# jar-of-fireflies.net
KiCad netlist of a schematic drawn in EAGLE
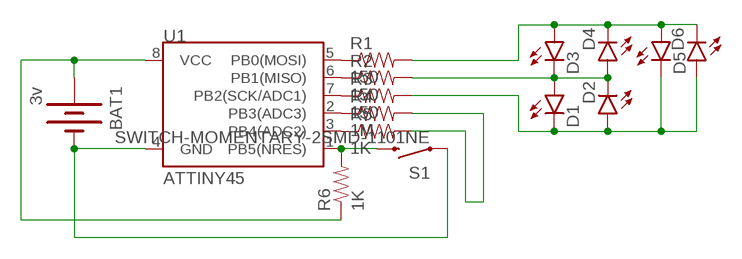
[diagram p0: schematic, sheet 1]

(export (version "E")
  (design (tool "Eeschema 10.0.6"))
  (components
    (comp (ref "BAT1")
      (value "3v")
      (footprint "eagle-import:BATTCOM_20MM_PTH")
      (libsource (lib "eagle-import") (part "BATTERY20PTH"))
    )
    (comp (ref "D1")
      (value "LED3MM")
      (footprint "eagle-import:LED3MM")
      (libsource (lib "eagle-import") (part "LED3MM"))
    )
    (comp (ref "D2")
      (value "LED3MM")
      (footprint "eagle-import:LED3MM")
      (libsource (lib "eagle-import") (part "LED3MM"))
    )
    (comp (ref "D3")
      (value "LED3MM")
      (footprint "eagle-import:LED3MM")
      (libsource (lib "eagle-import") (part "LED3MM"))
    )
    (comp (ref "D4")
      (value "LED3MM")
      (footprint "eagle-import:LED3MM")
      (libsource (lib "eagle-import") (part "LED3MM"))
    )
    (comp (ref "D5")
      (value "LED3MM")
      (footprint "eagle-import:LED3MM")
      (libsource (lib "eagle-import") (part "LED3MM"))
    )
    (comp (ref "D6")
      (value "LED3MM")
      (footprint "eagle-import:LED3MM")
      (libsource (lib "eagle-import") (part "LED3MM"))
    )
    (comp (ref "R1")
      (value "150")
      (footprint "eagle-import:AXIAL-0.4")
      (libsource (lib "eagle-import") (part "RESISTORPTH-1/4W"))
    )
    (comp (ref "R2")
      (value "150")
      (footprint "eagle-import:AXIAL-0.4")
      (libsource (lib "eagle-import") (part "RESISTORPTH-1/4W"))
    )
    (comp (ref "R3")
      (value "150")
      (footprint "eagle-import:AXIAL-0.4")
      (libsource (lib "eagle-import") (part "RESISTORPTH-1/4W"))
    )
    (comp (ref "R4")
      (value "1M")
      (footprint "eagle-import:AXIAL-0.4")
      (libsource (lib "eagle-import") (part "RESISTORPTH-1/4W"))
    )
    (comp (ref "R5")
      (value "1K")
      (footprint "eagle-import:AXIAL-0.4")
      (libsource (lib "eagle-import") (part "RESISTORPTH-1/4W"))
    )
    (comp (ref "R6")
      (value "1K")
      (footprint "eagle-import:AXIAL-0.4")
      (libsource (lib "eagle-import") (part "RESISTORPTH-1/4W"))
    )
    (comp (ref "S1")
      (value "SWITCH-MOMENTARY-2SMD-1101NE")
      (footprint "eagle-import:TACTILE-SWITCH-1101NE")
      (libsource (lib "eagle-import") (part "SWITCH-MOMENTARY-2SMD-1101NE"))
    )
    (comp (ref "U1")
      (value "ATTINY45")
      (footprint "eagle-import:DIP08")
      (libsource (lib "eagle-import") (part "ATTINY45TINY85-20-DIP"))
    )
  )
  (nets
    (net (code "1") (name "Net-(BAT1-+)") (class "Default")
      (node (ref "BAT1") (pin "1") (pinfunction "+_1") (pintype "power_in"))
      (node (ref "R6") (pin "P$1") (pinfunction "1_P$1") (pintype "passive"))
      (node (ref "U1") (pin "8") (pinfunction "VCC_8") (pintype "bidirectional"))
    )
    (net (code "2") (name "Net-(BAT1--)") (class "Default")
      (node (ref "BAT1") (pin "2") (pinfunction "-_2") (pintype "power_in"))
      (node (ref "S1") (pin "1") (pinfunction "1_1") (pintype "passive"))
      (node (ref "U1") (pin "4") (pinfunction "GND_4") (pintype "bidirectional"))
    )
    (net (code "3") (name "Net-(D1-C)") (class "Default")
      (node (ref "D1") (pin "K") (pinfunction "C_K") (pintype "passive"))
      (node (ref "D2") (pin "A") (pinfunction "A_A") (pintype "passive"))
      (node (ref "D5") (pin "K") (pinfunction "C_K") (pintype "passive"))
      (node (ref "D6") (pin "A") (pinfunction "A_A") (pintype "passive"))
      (node (ref "R3") (pin "P$2") (pinfunction "2_P$2") (pintype "passive"))
    )
    (net (code "4") (name "Net-(D2-C)") (class "Default")
      (node (ref "D1") (pin "A") (pinfunction "A_A") (pintype "passive"))
      (node (ref "D2") (pin "K") (pinfunction "C_K") (pintype "passive"))
      (node (ref "D3") (pin "K") (pinfunction "C_K") (pintype "passive"))
      (node (ref "D4") (pin "A") (pinfunction "A_A") (pintype "passive"))
      (node (ref "R2") (pin "P$2") (pinfunction "2_P$2") (pintype "passive"))
    )
    (net (code "5") (name "Net-(D4-C)") (class "Default")
      (node (ref "D3") (pin "A") (pinfunction "A_A") (pintype "passive"))
      (node (ref "D4") (pin "K") (pinfunction "C_K") (pintype "passive"))
      (node (ref "D5") (pin "A") (pinfunction "A_A") (pintype "passive"))
      (node (ref "D6") (pin "K") (pinfunction "C_K") (pintype "passive"))
      (node (ref "R1") (pin "P$2") (pinfunction "2_P$2") (pintype "passive"))
    )
    (net (code "6") (name "Net-(R1-1)") (class "Default")
      (node (ref "R1") (pin "P$1") (pinfunction "1_P$1") (pintype "passive"))
      (node (ref "U1") (pin "5") (pinfunction "PB0(MOSI)_5") (pintype "bidirectional"))
    )
    (net (code "7") (name "Net-(R2-1)") (class "Default")
      (node (ref "R2") (pin "P$1") (pinfunction "1_P$1") (pintype "passive"))
      (node (ref "U1") (pin "6") (pinfunction "PB1(MISO)_6") (pintype "bidirectional"))
    )
    (net (code "8") (name "Net-(R3-1)") (class "Default")
      (node (ref "R3") (pin "P$1") (pinfunction "1_P$1") (pintype "passive"))
      (node (ref "U1") (pin "7") (pinfunction "PB2(SCK/ADC1)_7") (pintype "bidirectional"))
    )
    (net (code "9") (name "Net-(R4-1)") (class "Default")
      (node (ref "R4") (pin "P$1") (pinfunction "1_P$1") (pintype "passive"))
      (node (ref "U1") (pin "2") (pinfunction "PB3(ADC3)_2") (pintype "bidirectional"))
    )
    (net (code "10") (name "Net-(R4-2)") (class "Default")
      (node (ref "R4") (pin "P$2") (pinfunction "2_P$2") (pintype "passive"))
      (node (ref "R5") (pin "P$2") (pinfunction "2_P$2") (pintype "passive"))
    )
    (net (code "11") (name "Net-(R5-1)") (class "Default")
      (node (ref "R5") (pin "P$1") (pinfunction "1_P$1") (pintype "passive"))
      (node (ref "U1") (pin "3") (pinfunction "PB4(ADC2)_3") (pintype "bidirectional"))
    )
    (net (code "12") (name "Net-(R6-2)") (class "Default")
      (node (ref "R6") (pin "P$2") (pinfunction "2_P$2") (pintype "passive"))
      (node (ref "S1") (pin "2") (pinfunction "2_2") (pintype "passive"))
      (node (ref "U1") (pin "1") (pinfunction "PB5(NRES)_1") (pintype "bidirectional"))
    )
  )
)
